# Schatten4.net
KiCad netlist of a schematic drawn in EAGLE
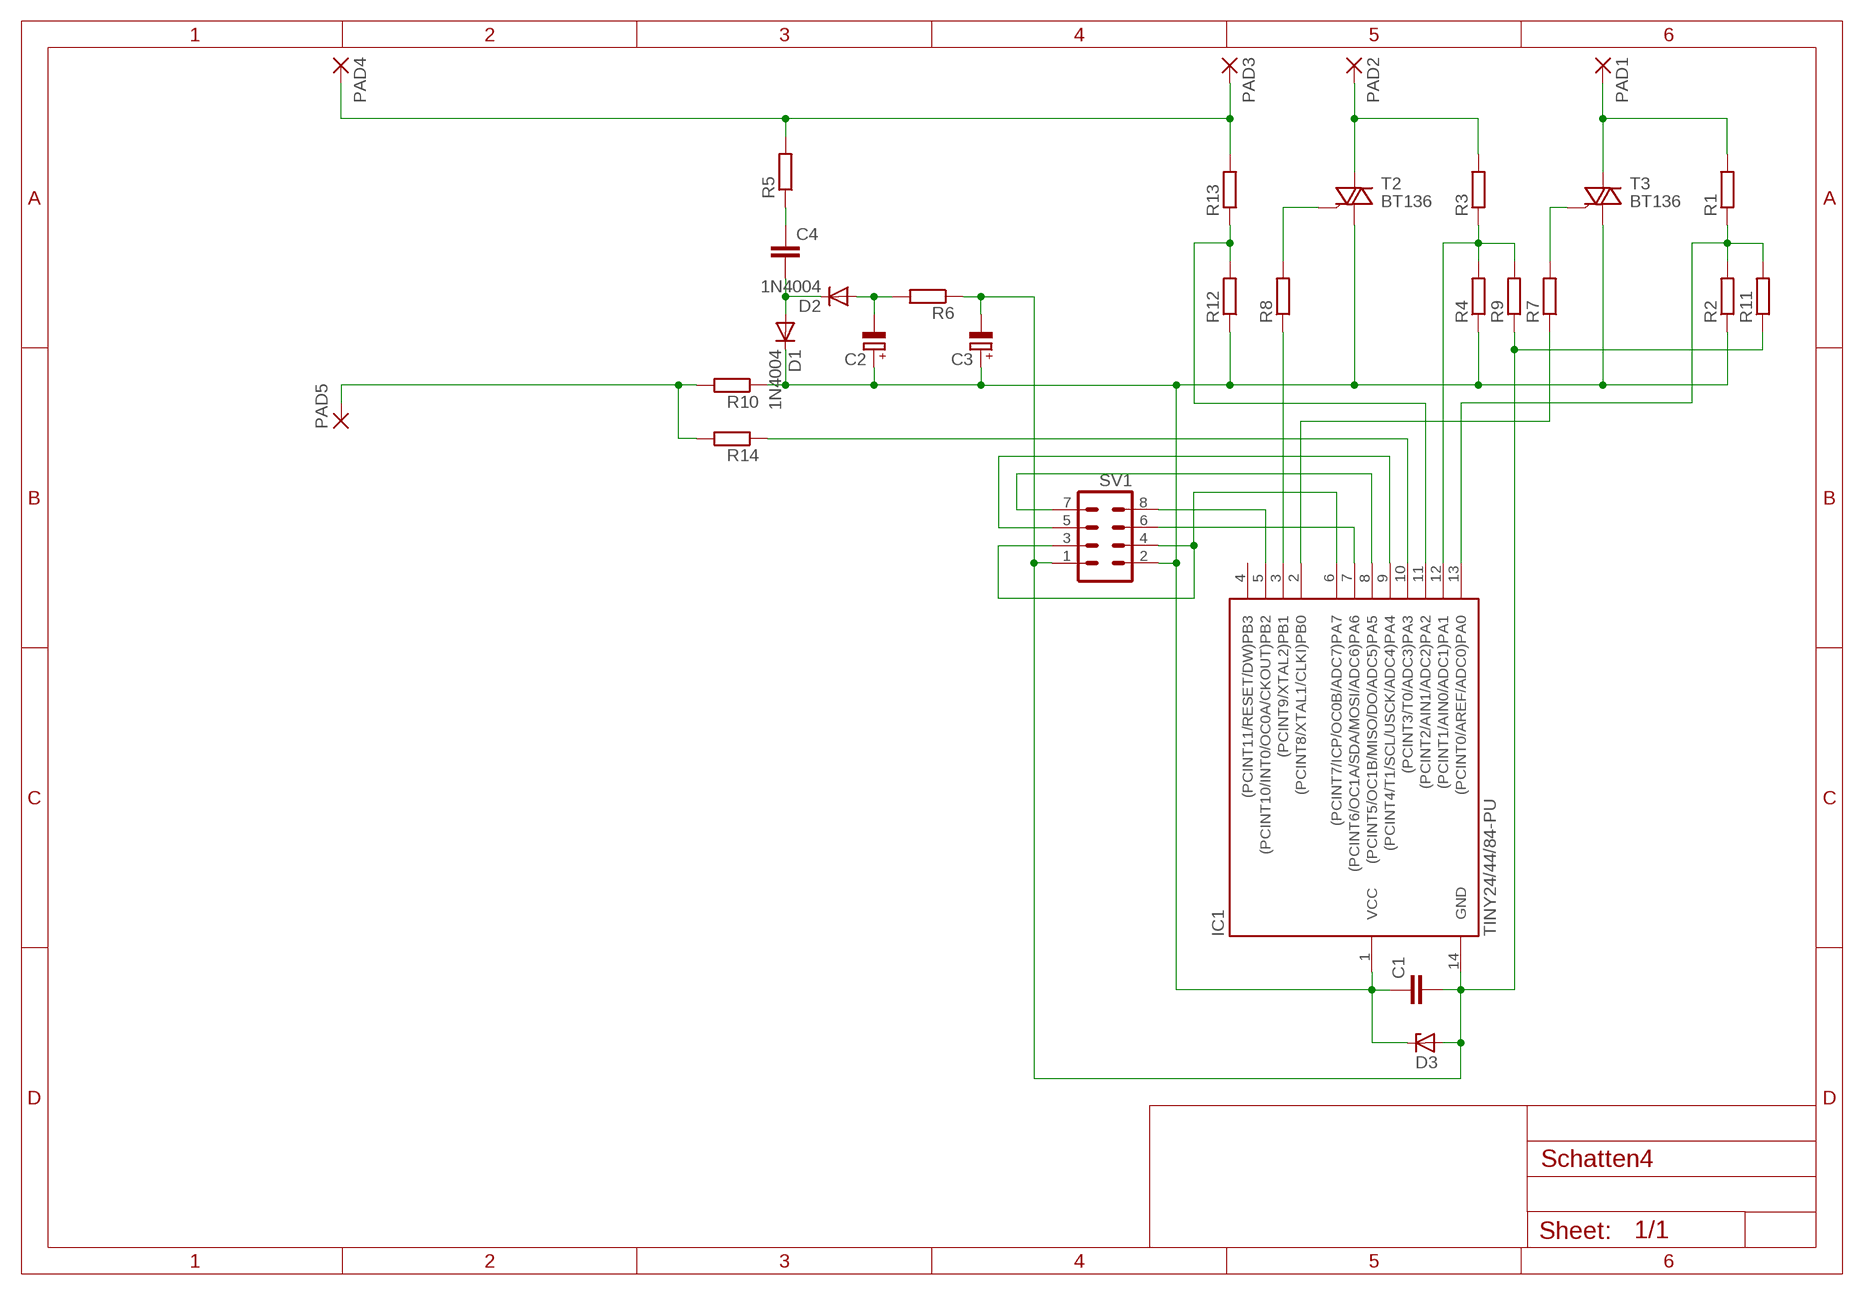
[diagram p0: schematic, sheet 1]

(export (version "E")
  (design (tool "Eeschema 10.0.6"))
  (components
    (comp (ref "C1")
      (value "C-EUC3225")
      (footprint "eagle-import:C3225")
      (libsource (lib "eagle-import") (part "C-EUC3225"))
    )
    (comp (ref "C2")
      (value "CPOL-EUE5-8.5")
      (footprint "eagle-import:E5-8,5")
      (libsource (lib "eagle-import") (part "CPOL-EUE5-8.5"))
    )
    (comp (ref "C3")
      (value "CPOL-EUE5-8.5")
      (footprint "eagle-import:E5-8,5")
      (libsource (lib "eagle-import") (part "CPOL-EUE5-8.5"))
    )
    (comp (ref "C4")
      (value "C-EU150-064X183")
      (footprint "eagle-import:C150-064X183")
      (libsource (lib "eagle-import") (part "C-EU150-064X183"))
    )
    (comp (ref "D1")
      (value "1N4004")
      (footprint "eagle-import:DO41-10")
      (libsource (lib "eagle-import") (part "1N4004"))
    )
    (comp (ref "D2")
      (value "1N4004")
      (footprint "eagle-import:DO41-10")
      (libsource (lib "eagle-import") (part "1N4004"))
    )
    (comp (ref "D3")
      (value "ZENER-DIODEZD-7.5")
      (footprint "eagle-import:ZDIO-7.5")
      (libsource (lib "eagle-import") (part "ZENER-DIODEZD-7.5"))
    )
    (comp (ref "IC1")
      (value "TINY24/44/84-PU")
      (footprint "eagle-import:DIL14")
      (libsource (lib "eagle-import") (part "TINY24/44/84-PU"))
    )
    (comp (ref "PAD1")
      (value "1,6/0,9")
      (footprint "eagle-import:1,6_0,9")
      (libsource (lib "eagle-import") (part "1,6/0,9"))
    )
    (comp (ref "PAD2")
      (value "1,6/0,9")
      (footprint "eagle-import:1,6_0,9")
      (libsource (lib "eagle-import") (part "1,6/0,9"))
    )
    (comp (ref "PAD3")
      (value "1,6/0,9")
      (footprint "eagle-import:1,6_0,9")
      (libsource (lib "eagle-import") (part "1,6/0,9"))
    )
    (comp (ref "PAD4")
      (value "1,6/0,9")
      (footprint "eagle-import:1,6_0,9")
      (libsource (lib "eagle-import") (part "1,6/0,9"))
    )
    (comp (ref "PAD5")
      (value "1,6/0,9")
      (footprint "eagle-import:1,6_0,9")
      (libsource (lib "eagle-import") (part "1,6/0,9"))
    )
    (comp (ref "R1")
      (value "R-EU_0207/10")
      (footprint "eagle-import:0207_10")
      (libsource (lib "eagle-import") (part "R-EU_0207/10"))
    )
    (comp (ref "R2")
      (value "R-EU_0207/10")
      (footprint "eagle-import:0207_10")
      (libsource (lib "eagle-import") (part "R-EU_0207/10"))
    )
    (comp (ref "R3")
      (value "R-EU_0207/10")
      (footprint "eagle-import:0207_10")
      (libsource (lib "eagle-import") (part "R-EU_0207/10"))
    )
    (comp (ref "R4")
      (value "R-EU_0207/10")
      (footprint "eagle-import:0207_10")
      (libsource (lib "eagle-import") (part "R-EU_0207/10"))
    )
    (comp (ref "R5")
      (value "R-EU_0207/10")
      (footprint "eagle-import:0207_10")
      (libsource (lib "eagle-import") (part "R-EU_0207/10"))
    )
    (comp (ref "R6")
      (value "R-EU_0207/10")
      (footprint "eagle-import:0207_10")
      (libsource (lib "eagle-import") (part "R-EU_0207/10"))
    )
    (comp (ref "R7")
      (value "R-EU_0207/10")
      (footprint "eagle-import:0207_10")
      (libsource (lib "eagle-import") (part "R-EU_0207/10"))
    )
    (comp (ref "R8")
      (value "R-EU_0207/10")
      (footprint "eagle-import:0207_10")
      (libsource (lib "eagle-import") (part "R-EU_0207/10"))
    )
    (comp (ref "R9")
      (value "R-EU_0207/10")
      (footprint "eagle-import:0207_10")
      (libsource (lib "eagle-import") (part "R-EU_0207/10"))
    )
    (comp (ref "R10")
      (value "R-EU_0207/10")
      (footprint "eagle-import:0207_10")
      (libsource (lib "eagle-import") (part "R-EU_0207/10"))
    )
    (comp (ref "R11")
      (value "R-EU_0207/10")
      (footprint "eagle-import:0207_10")
      (libsource (lib "eagle-import") (part "R-EU_0207/10"))
    )
    (comp (ref "R12")
      (value "R-EU_0207/10")
      (footprint "eagle-import:0207_10")
      (libsource (lib "eagle-import") (part "R-EU_0207/10"))
    )
    (comp (ref "R13")
      (value "R-EU_0207/10")
      (footprint "eagle-import:0207_10")
      (libsource (lib "eagle-import") (part "R-EU_0207/10"))
    )
    (comp (ref "R14")
      (value "R-EU_0207/10")
      (footprint "eagle-import:0207_10")
      (libsource (lib "eagle-import") (part "R-EU_0207/10"))
    )
    (comp (ref "SV1")
      (value "MA04-2")
      (footprint "eagle-import:MA04-2")
      (libsource (lib "eagle-import") (part "MA04-2"))
    )
    (comp (ref "T2")
      (value "BT136")
      (footprint "eagle-import:TO220AB")
      (libsource (lib "eagle-import") (part "BT136"))
    )
    (comp (ref "T3")
      (value "BT136")
      (footprint "eagle-import:TO220AB")
      (libsource (lib "eagle-import") (part "BT136"))
    )
  )
  (nets
    (net (code "1") (name "Net-(C2-Pad-)") (class "Default")
      (node (ref "C2") (pin "-") (pinfunction "-_-") (pintype "passive"))
      (node (ref "D2") (pin "A") (pinfunction "A_A") (pintype "passive"))
      (node (ref "R6") (pin "2") (pinfunction "2_2") (pintype "passive"))
    )
    (net (code "2") (name "Net-(C4-Pad1)") (class "Default")
      (node (ref "C4") (pin "1") (pinfunction "1_1") (pintype "passive"))
      (node (ref "R5") (pin "1") (pinfunction "1_1") (pintype "passive"))
    )
    (net (code "3") (name "Net-(C4-Pad2)") (class "Default")
      (node (ref "C4") (pin "2") (pinfunction "2_2") (pintype "passive"))
      (node (ref "D1") (pin "A") (pinfunction "A_A") (pintype "passive"))
      (node (ref "D2") (pin "C") (pinfunction "C_C") (pintype "passive"))
    )
    (net (code "4") (name "Net-(IC1-(PCINT0{slash}AREF{slash}ADC0)PA0)") (class "Default")
      (node (ref "IC1") (pin "13") (pinfunction "(PCINT0/AREF/ADC0)PA0_13") (pintype "bidirectional"))
      (node (ref "R1") (pin "1") (pinfunction "1_1") (pintype "passive"))
      (node (ref "R11") (pin "2") (pinfunction "2_2") (pintype "passive"))
      (node (ref "R2") (pin "2") (pinfunction "2_2") (pintype "passive"))
    )
    (net (code "5") (name "Net-(IC1-(PCINT1{slash}AIN0{slash}ADC1)PA1)") (class "Default")
      (node (ref "IC1") (pin "12") (pinfunction "(PCINT1/AIN0/ADC1)PA1_12") (pintype "bidirectional"))
      (node (ref "R3") (pin "1") (pinfunction "1_1") (pintype "passive"))
      (node (ref "R4") (pin "2") (pinfunction "2_2") (pintype "passive"))
      (node (ref "R9") (pin "2") (pinfunction "2_2") (pintype "passive"))
    )
    (net (code "6") (name "Net-(IC1-(PCINT2{slash}AIN1{slash}ADC2)PA2)") (class "Default")
      (node (ref "IC1") (pin "11") (pinfunction "(PCINT2/AIN1/ADC2)PA2_11") (pintype "bidirectional"))
      (node (ref "R12") (pin "2") (pinfunction "2_2") (pintype "passive"))
      (node (ref "R13") (pin "1") (pinfunction "1_1") (pintype "passive"))
    )
    (net (code "7") (name "Net-(IC1-(PCINT3{slash}T0{slash}ADC3)PA3)") (class "Default")
      (node (ref "IC1") (pin "10") (pinfunction "(PCINT3/T0/ADC3)PA3_10") (pintype "bidirectional"))
      (node (ref "R14") (pin "1") (pinfunction "1_1") (pintype "passive"))
    )
    (net (code "8") (name "Net-(IC1-(PCINT4{slash}T1{slash}SCL{slash}USCK{slash}ADC4)PA4)") (class "Default")
      (node (ref "IC1") (pin "9") (pinfunction "(PCINT4/T1/SCL/USCK/ADC4)PA4_9") (pintype "bidirectional"))
      (node (ref "SV1") (pin "5") (pinfunction "5_5") (pintype "passive"))
    )
    (net (code "9") (name "Net-(IC1-(PCINT5{slash}OC1B{slash}MISO{slash}DO{slash}ADC5)PA5)") (class "Default")
      (node (ref "IC1") (pin "8") (pinfunction "(PCINT5/OC1B/MISO/DO/ADC5)PA5_8") (pintype "bidirectional"))
      (node (ref "SV1") (pin "7") (pinfunction "7_7") (pintype "passive"))
    )
    (net (code "10") (name "Net-(IC1-(PCINT6{slash}OC1A{slash}SDA{slash}MOSI{slash}ADC6)PA6)") (class "Default")
      (node (ref "IC1") (pin "7") (pinfunction "(PCINT6/OC1A/SDA/MOSI/ADC6)PA6_7") (pintype "bidirectional"))
      (node (ref "SV1") (pin "6") (pinfunction "6_6") (pintype "passive"))
    )
    (net (code "11") (name "Net-(IC1-(PCINT7{slash}ICP{slash}OC0B{slash}ADC7)PA7)") (class "Default")
      (node (ref "IC1") (pin "6") (pinfunction "(PCINT7/ICP/OC0B/ADC7)PA7_6") (pintype "bidirectional"))
      (node (ref "SV1") (pin "3") (pinfunction "3_3") (pintype "passive"))
      (node (ref "SV1") (pin "4") (pinfunction "4_4") (pintype "passive"))
    )
    (net (code "12") (name "Net-(IC1-(PCINT8{slash}XTAL1{slash}CLKI)PB0)") (class "Default")
      (node (ref "IC1") (pin "2") (pinfunction "(PCINT8/XTAL1/CLKI)PB0_2") (pintype "bidirectional"))
      (node (ref "R7") (pin "1") (pinfunction "1_1") (pintype "passive"))
    )
    (net (code "13") (name "Net-(IC1-(PCINT9{slash}XTAL2)PB1)") (class "Default")
      (node (ref "IC1") (pin "3") (pinfunction "(PCINT9/XTAL2)PB1_3") (pintype "bidirectional"))
      (node (ref "R8") (pin "1") (pinfunction "1_1") (pintype "passive"))
    )
    (net (code "14") (name "Net-(IC1-(PCINT10{slash}INT0{slash}OC0A{slash}CKOUT)PB2)") (class "Default")
      (node (ref "IC1") (pin "5") (pinfunction "(PCINT10/INT0/OC0A/CKOUT)PB2_5") (pintype "bidirectional"))
      (node (ref "SV1") (pin "8") (pinfunction "8_8") (pintype "passive"))
    )
    (net (code "15") (name "Net-(IC1-GND)") (class "Default")
      (node (ref "C1") (pin "2") (pinfunction "2_2") (pintype "passive"))
      (node (ref "C3") (pin "-") (pinfunction "-_-") (pintype "passive"))
      (node (ref "D3") (pin "A") (pinfunction "A_A") (pintype "passive"))
      (node (ref "IC1") (pin "14") (pinfunction "GND_14") (pintype "power_in"))
      (node (ref "R11") (pin "1") (pinfunction "1_1") (pintype "passive"))
      (node (ref "R6") (pin "1") (pinfunction "1_1") (pintype "passive"))
      (node (ref "R9") (pin "1") (pinfunction "1_1") (pintype "passive"))
      (node (ref "SV1") (pin "1") (pinfunction "1_1") (pintype "passive"))
    )
    (net (code "16") (name "Net-(IC1-VCC)") (class "Default")
      (node (ref "C1") (pin "1") (pinfunction "1_1") (pintype "passive"))
      (node (ref "C2") (pin "+") (pinfunction "+_+") (pintype "passive"))
      (node (ref "C3") (pin "+") (pinfunction "+_+") (pintype "passive"))
      (node (ref "D1") (pin "C") (pinfunction "C_C") (pintype "passive"))
      (node (ref "D3") (pin "C") (pinfunction "C_C") (pintype "passive"))
      (node (ref "IC1") (pin "1") (pinfunction "VCC_1") (pintype "power_in"))
      (node (ref "R10") (pin "1") (pinfunction "1_1") (pintype "passive"))
      (node (ref "R12") (pin "1") (pinfunction "1_1") (pintype "passive"))
      (node (ref "R2") (pin "1") (pinfunction "1_1") (pintype "passive"))
      (node (ref "R4") (pin "1") (pinfunction "1_1") (pintype "passive"))
      (node (ref "SV1") (pin "2") (pinfunction "2_2") (pintype "passive"))
      (node (ref "T2") (pin "1") (pinfunction "A1_1") (pintype "passive"))
      (node (ref "T3") (pin "1") (pinfunction "A1_1") (pintype "passive"))
    )
    (net (code "17") (name "Net-(PAD1-P)") (class "Default")
      (node (ref "PAD1") (pin "1") (pinfunction "P_1") (pintype "passive"))
      (node (ref "R1") (pin "2") (pinfunction "2_2") (pintype "passive"))
      (node (ref "T3") (pin "2") (pinfunction "A2_2") (pintype "passive"))
    )
    (net (code "18") (name "Net-(PAD2-P)") (class "Default")
      (node (ref "PAD2") (pin "1") (pinfunction "P_1") (pintype "passive"))
      (node (ref "R3") (pin "2") (pinfunction "2_2") (pintype "passive"))
      (node (ref "T2") (pin "2") (pinfunction "A2_2") (pintype "passive"))
    )
    (net (code "19") (name "Net-(PAD3-P)") (class "Default")
      (node (ref "PAD3") (pin "1") (pinfunction "P_1") (pintype "passive"))
      (node (ref "PAD4") (pin "1") (pinfunction "P_1") (pintype "passive"))
      (node (ref "R13") (pin "2") (pinfunction "2_2") (pintype "passive"))
      (node (ref "R5") (pin "2") (pinfunction "2_2") (pintype "passive"))
    )
    (net (code "20") (name "Net-(PAD5-P)") (class "Default")
      (node (ref "PAD5") (pin "1") (pinfunction "P_1") (pintype "passive"))
      (node (ref "R10") (pin "2") (pinfunction "2_2") (pintype "passive"))
      (node (ref "R14") (pin "2") (pinfunction "2_2") (pintype "passive"))
    )
    (net (code "21") (name "Net-(T2-G)") (class "Default")
      (node (ref "R8") (pin "2") (pinfunction "2_2") (pintype "passive"))
      (node (ref "T2") (pin "3") (pinfunction "G_3") (pintype "passive"))
    )
    (net (code "22") (name "Net-(T3-G)") (class "Default")
      (node (ref "R7") (pin "2") (pinfunction "2_2") (pintype "passive"))
      (node (ref "T3") (pin "3") (pinfunction "G_3") (pintype "passive"))
    )
    (net (code "23") (name "unconnected-(IC1-(PCINT11{slash}RESET{slash}DW)PB3-Pad4)") (class "Default")
      (node (ref "IC1") (pin "4") (pinfunction "(PCINT11/RESET/DW)PB3_4") (pintype "bidirectional"))
    )
  )
)
